# smoggie.net
KiCad netlist of a schematic drawn in EAGLE
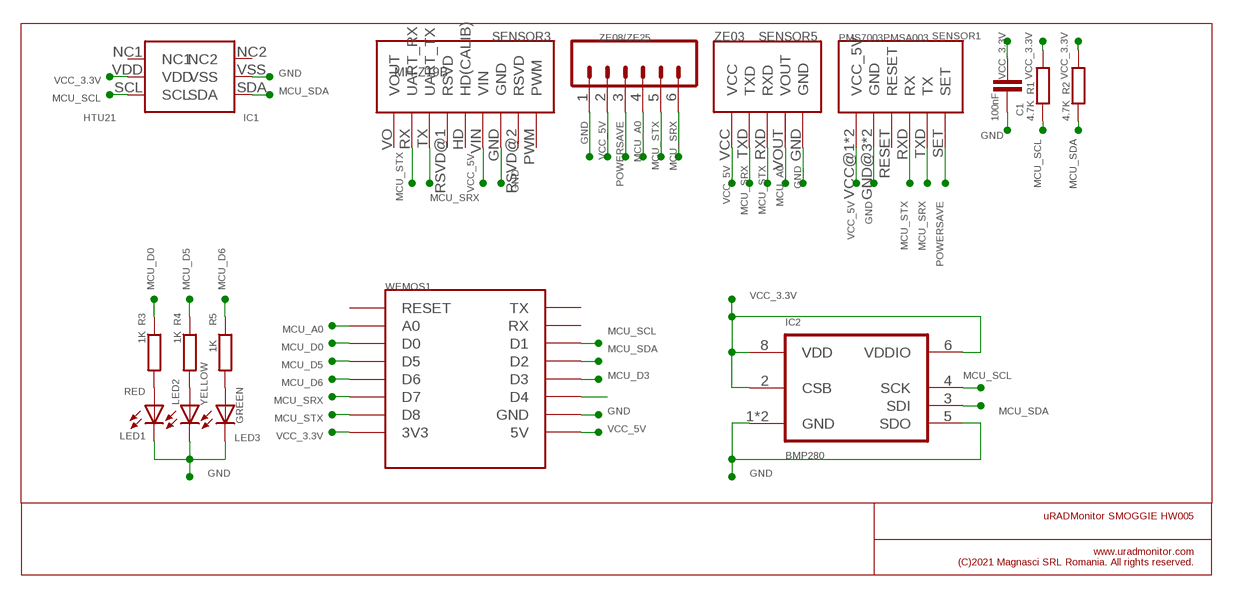
[diagram p0: schematic, sheet 1]

(export (version "E")
  (design (tool "Eeschema 10.0.6"))
  (components
    (comp (ref "C1")
      (value "100nF")
      (footprint "eagle-import:C0603")
      (libsource (lib "eagle-import") (part "C-EUC0603"))
    )
    (comp (ref "IC1")
      (value "HTU21")
      (footprint "eagle-import:SHT21")
      (libsource (lib "eagle-import") (part "SHT21SMDSMD"))
    )
    (comp (ref "IC2")
      (value "BMP280")
      (footprint "eagle-import:BMP280")
      (libsource (lib "eagle-import") (part "BMP280"))
    )
    (comp (ref "LED1")
      (value "RED")
      (footprint "eagle-import:SML0603")
      (libsource (lib "eagle-import") (part "LEDSML0603"))
    )
    (comp (ref "LED2")
      (value "YELLOW")
      (footprint "eagle-import:SML0603")
      (libsource (lib "eagle-import") (part "LEDSML0603"))
    )
    (comp (ref "LED3")
      (value "GREEN")
      (footprint "eagle-import:SML0603")
      (libsource (lib "eagle-import") (part "LEDSML0603"))
    )
    (comp (ref "R1")
      (value "4.7K")
      (footprint "eagle-import:R0603")
      (libsource (lib "eagle-import") (part "resistor_348_R-EU_R0603"))
    )
    (comp (ref "R2")
      (value "4.7K")
      (footprint "eagle-import:R0603")
      (libsource (lib "eagle-import") (part "resistor_348_R-EU_R0603"))
    )
    (comp (ref "R3")
      (value "1K")
      (footprint "eagle-import:R0603")
      (libsource (lib "eagle-import") (part "R-EU_R0603"))
    )
    (comp (ref "R4")
      (value "1K")
      (footprint "eagle-import:R0603")
      (libsource (lib "eagle-import") (part "R-EU_R0603"))
    )
    (comp (ref "R5")
      (value "1K")
      (footprint "eagle-import:R0603")
      (libsource (lib "eagle-import") (part "R-EU_R0603"))
    )
    (comp (ref "SENSOR1")
      (value "PMS7003PMSA003")
      (footprint "eagle-import:PMSA003")
      (libsource (lib "eagle-import") (part "PMS7003PMSA003"))
    )
    (comp (ref "SENSOR3")
      (value "MH-Z19B")
      (footprint "eagle-import:MH-Z19B")
      (libsource (lib "eagle-import") (part "MH-Z19B"))
    )
    (comp (ref "SENSOR5")
      (value "ZE03")
      (footprint "eagle-import:ZE03")
      (libsource (lib "eagle-import") (part "ZE03"))
    )
    (comp (ref "WEMOS1")
      (value "11")
      (footprint "eagle-import:WEMOS-D1-MINI")
      (libsource (lib "eagle-import") (part "WEMOS-D1-MINI"))
    )
    (comp (ref "ZE08/ZE25")
      (value "M06SIP")
      (footprint "eagle-import:1X06")
      (libsource (lib "eagle-import") (part "M06SIP"))
    )
  )
  (nets
    (net (code "1") (name "/GND") (class "Default")
      (node (ref "C1") (pin "1") (pinfunction "1_1") (pintype "passive"))
      (node (ref "IC1") (pin "VSS") (pinfunction "VSS_VSS") (pintype "output"))
      (node (ref "IC2") (pin "1") (pinfunction "GND_1") (pintype "power_in"))
      (node (ref "IC2") (pin "5") (pinfunction "SDO_5") (pintype "input"))
      (node (ref "IC2") (pin "7") (pinfunction "GND_7") (pintype "power_in"))
      (node (ref "LED1") (pin "C") (pinfunction "C_C") (pintype "passive"))
      (node (ref "LED2") (pin "C") (pinfunction "C_C") (pintype "passive"))
      (node (ref "LED3") (pin "C") (pinfunction "C_C") (pintype "passive"))
      (node (ref "SENSOR1") (pin "GND@3") (pinfunction "GND_GND@3") (pintype "bidirectional"))
      (node (ref "SENSOR1") (pin "GND@4") (pinfunction "GND_GND@4") (pintype "bidirectional"))
      (node (ref "SENSOR3") (pin "GND") (pinfunction "GND_GND") (pintype "bidirectional"))
      (node (ref "SENSOR5") (pin "GND") (pinfunction "GND_GND") (pintype "bidirectional"))
      (node (ref "WEMOS1") (pin "GND") (pinfunction "GND_GND") (pintype "bidirectional"))
      (node (ref "ZE08/ZE25") (pin "1") (pinfunction "1_1") (pintype "passive"))
    )
    (net (code "2") (name "/MCU_A0") (class "Default")
      (node (ref "SENSOR5") (pin "VOUT") (pinfunction "VOUT_VOUT") (pintype "bidirectional"))
      (node (ref "WEMOS1") (pin "A0") (pinfunction "A0_A0") (pintype "bidirectional"))
      (node (ref "ZE08/ZE25") (pin "4") (pinfunction "4_4") (pintype "passive"))
    )
    (net (code "3") (name "/MCU_D0") (class "Default")
      (node (ref "R3") (pin "1") (pinfunction "1_1") (pintype "passive"))
      (node (ref "WEMOS1") (pin "D0") (pinfunction "D0_D0") (pintype "bidirectional"))
    )
    (net (code "4") (name "/MCU_D3") (class "Default")
      (node (ref "WEMOS1") (pin "D3") (pinfunction "D3_D3") (pintype "bidirectional"))
    )
    (net (code "5") (name "/MCU_D5") (class "Default")
      (node (ref "R4") (pin "1") (pinfunction "1_1") (pintype "passive"))
      (node (ref "WEMOS1") (pin "D5") (pinfunction "D5_D5") (pintype "bidirectional"))
    )
    (net (code "6") (name "/MCU_D6") (class "Default")
      (node (ref "R5") (pin "1") (pinfunction "1_1") (pintype "passive"))
      (node (ref "WEMOS1") (pin "D6") (pinfunction "D6_D6") (pintype "bidirectional"))
    )
    (net (code "7") (name "/MCU_SCL") (class "Default")
      (node (ref "IC1") (pin "SCL") (pinfunction "SCL_SCL") (pintype "power_in"))
      (node (ref "IC2") (pin "4") (pinfunction "SCK_4") (pintype "bidirectional"))
      (node (ref "R1") (pin "2") (pinfunction "2_2") (pintype "passive"))
      (node (ref "WEMOS1") (pin "D1") (pinfunction "D1_D1") (pintype "bidirectional"))
    )
    (net (code "8") (name "/MCU_SDA") (class "Default")
      (node (ref "IC1") (pin "SDA") (pinfunction "SDA_SDA") (pintype "power_in"))
      (node (ref "IC2") (pin "3") (pinfunction "SDI_3") (pintype "bidirectional"))
      (node (ref "R2") (pin "2") (pinfunction "2_2") (pintype "passive"))
      (node (ref "WEMOS1") (pin "D2") (pinfunction "D2_D2") (pintype "bidirectional"))
    )
    (net (code "9") (name "/MCU_SRX") (class "Default")
      (node (ref "SENSOR1") (pin "TXD") (pinfunction "TX_TXD") (pintype "bidirectional"))
      (node (ref "SENSOR3") (pin "TX") (pinfunction "UART_TX_TX") (pintype "bidirectional"))
      (node (ref "SENSOR5") (pin "TXD") (pinfunction "TXD_TXD") (pintype "bidirectional"))
      (node (ref "WEMOS1") (pin "D7") (pinfunction "D7_D7") (pintype "bidirectional"))
      (node (ref "ZE08/ZE25") (pin "6") (pinfunction "6_6") (pintype "passive"))
    )
    (net (code "10") (name "/MCU_STX") (class "Default")
      (node (ref "SENSOR1") (pin "RXD") (pinfunction "RX_RXD") (pintype "bidirectional"))
      (node (ref "SENSOR3") (pin "RX") (pinfunction "UART_RX_RX") (pintype "bidirectional"))
      (node (ref "SENSOR5") (pin "RXD") (pinfunction "RXD_RXD") (pintype "bidirectional"))
      (node (ref "WEMOS1") (pin "D8") (pinfunction "D8_D8") (pintype "bidirectional"))
      (node (ref "ZE08/ZE25") (pin "5") (pinfunction "5_5") (pintype "passive"))
    )
    (net (code "11") (name "/POWERSAVE") (class "Default")
      (node (ref "SENSOR1") (pin "SET") (pinfunction "SET_SET") (pintype "bidirectional"))
      (node (ref "ZE08/ZE25") (pin "3") (pinfunction "3_3") (pintype "passive"))
    )
    (net (code "12") (name "/VCC_3.3V") (class "Default")
      (node (ref "C1") (pin "2") (pinfunction "2_2") (pintype "passive"))
      (node (ref "IC1") (pin "VDD") (pinfunction "VDD_VDD") (pintype "input"))
      (node (ref "IC2") (pin "2") (pinfunction "CSB_2") (pintype "input"))
      (node (ref "IC2") (pin "6") (pinfunction "VDDIO_6") (pintype "power_in"))
      (node (ref "IC2") (pin "8") (pinfunction "VDD_8") (pintype "power_in"))
      (node (ref "R1") (pin "1") (pinfunction "1_1") (pintype "passive"))
      (node (ref "R2") (pin "1") (pinfunction "1_1") (pintype "passive"))
      (node (ref "WEMOS1") (pin "3V3") (pinfunction "3V3_3V3") (pintype "bidirectional"))
    )
    (net (code "13") (name "/VCC_5V") (class "Default")
      (node (ref "SENSOR1") (pin "VCC@1") (pinfunction "VCC_5V_VCC@1") (pintype "bidirectional"))
      (node (ref "SENSOR1") (pin "VCC@2") (pinfunction "VCC_5V_VCC@2") (pintype "bidirectional"))
      (node (ref "SENSOR3") (pin "VIN") (pinfunction "VIN_VIN") (pintype "bidirectional"))
      (node (ref "SENSOR5") (pin "VCC") (pinfunction "VCC_VCC") (pintype "bidirectional"))
      (node (ref "WEMOS1") (pin "5V") (pinfunction "5V_5V") (pintype "bidirectional"))
      (node (ref "ZE08/ZE25") (pin "2") (pinfunction "2_2") (pintype "passive"))
    )
    (net (code "14") (name "Net-(LED1-PadA)") (class "Default")
      (node (ref "LED1") (pin "A") (pinfunction "A_A") (pintype "passive"))
      (node (ref "R3") (pin "2") (pinfunction "2_2") (pintype "passive"))
    )
    (net (code "15") (name "Net-(LED2-PadA)") (class "Default")
      (node (ref "LED2") (pin "A") (pinfunction "A_A") (pintype "passive"))
      (node (ref "R4") (pin "2") (pinfunction "2_2") (pintype "passive"))
    )
    (net (code "16") (name "Net-(LED3-PadA)") (class "Default")
      (node (ref "LED3") (pin "A") (pinfunction "A_A") (pintype "passive"))
      (node (ref "R5") (pin "2") (pinfunction "2_2") (pintype "passive"))
    )
    (net (code "17") (name "unconnected-(IC1-PadNC1)") (class "Default")
      (node (ref "IC1") (pin "NC1") (pinfunction "NC1_NC1") (pintype "no_connect"))
    )
    (net (code "18") (name "unconnected-(IC1-PadNC2)") (class "Default")
      (node (ref "IC1") (pin "NC2") (pinfunction "NC2_NC2") (pintype "no_connect"))
    )
    (net (code "19") (name "unconnected-(SENSOR1-PadRESET)") (class "Default")
      (node (ref "SENSOR1") (pin "RESET") (pinfunction "RESET_RESET") (pintype "bidirectional"))
    )
    (net (code "20") (name "unconnected-(SENSOR3-HD(CALIB)-PadHD)") (class "Default")
      (node (ref "SENSOR3") (pin "HD") (pinfunction "HD(CALIB)_HD") (pintype "bidirectional"))
    )
    (net (code "21") (name "unconnected-(SENSOR3-PadPWM)") (class "Default")
      (node (ref "SENSOR3") (pin "PWM") (pinfunction "PWM_PWM") (pintype "bidirectional"))
    )
    (net (code "22") (name "unconnected-(SENSOR3-RSVD-PadRSVD@1)") (class "Default")
      (node (ref "SENSOR3") (pin "RSVD@1") (pinfunction "RSVD_RSVD@1") (pintype "bidirectional"))
    )
    (net (code "23") (name "unconnected-(SENSOR3-RSVD-PadRSVD@2)") (class "Default")
      (node (ref "SENSOR3") (pin "RSVD@2") (pinfunction "RSVD_RSVD@2") (pintype "bidirectional"))
    )
    (net (code "24") (name "unconnected-(SENSOR3-VOUT-PadVO)") (class "Default")
      (node (ref "SENSOR3") (pin "VO") (pinfunction "VOUT_VO") (pintype "bidirectional"))
    )
    (net (code "25") (name "unconnected-(WEMOS1-PadD4)") (class "Default")
      (node (ref "WEMOS1") (pin "D4") (pinfunction "D4_D4") (pintype "bidirectional"))
    )
    (net (code "26") (name "unconnected-(WEMOS1-PadRESET)") (class "Default")
      (node (ref "WEMOS1") (pin "RESET") (pinfunction "RESET_RESET") (pintype "bidirectional"))
    )
    (net (code "27") (name "unconnected-(WEMOS1-PadRX)") (class "Default")
      (node (ref "WEMOS1") (pin "RX") (pinfunction "RX_RX") (pintype "bidirectional"))
    )
    (net (code "28") (name "unconnected-(WEMOS1-PadTX)") (class "Default")
      (node (ref "WEMOS1") (pin "TX") (pinfunction "TX_TX") (pintype "bidirectional"))
    )
  )
)
